# CT100-array.net
KiCad netlist of a schematic drawn in Altium Designer
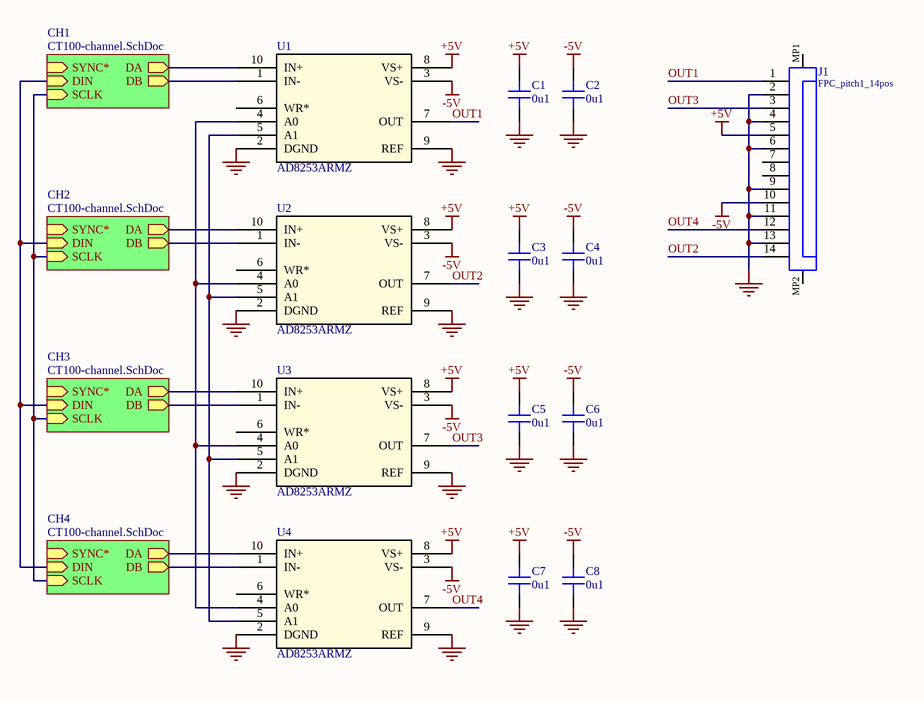
[diagram p0: CT100-array.SchDoc]

(export (version "E")
  (design (tool "Eeschema 10.0.6"))
  (components
    (comp (ref "C1")
      (value "0u1")
      (footprint "CAP_0402")
      (description "Capacitor SMD 0402")
      (fields (field (name "VOLTAGE") "50V"))
      (libsource (lib "symbols") (part "CAP_0402"))
    )
    (comp (ref "C2")
      (value "0u1")
      (footprint "CAP_0402")
      (description "Capacitor SMD 0402")
      (fields (field (name "VOLTAGE") "50V"))
      (libsource (lib "symbols") (part "CAP_0402"))
    )
    (comp (ref "C3")
      (value "0u1")
      (footprint "CAP_0402")
      (description "Capacitor SMD 0402")
      (fields (field (name "VOLTAGE") "50V"))
      (libsource (lib "symbols") (part "CAP_0402"))
    )
    (comp (ref "C4")
      (value "0u1")
      (footprint "CAP_0402")
      (description "Capacitor SMD 0402")
      (fields (field (name "VOLTAGE") "50V"))
      (libsource (lib "symbols") (part "CAP_0402"))
    )
    (comp (ref "C5")
      (value "0u1")
      (footprint "CAP_0402")
      (description "Capacitor SMD 0402")
      (fields (field (name "VOLTAGE") "50V"))
      (libsource (lib "symbols") (part "CAP_0402"))
    )
    (comp (ref "C6")
      (value "0u1")
      (footprint "CAP_0402")
      (description "Capacitor SMD 0402")
      (fields (field (name "VOLTAGE") "50V"))
      (libsource (lib "symbols") (part "CAP_0402"))
    )
    (comp (ref "C7")
      (value "0u1")
      (footprint "CAP_0402")
      (description "Capacitor SMD 0402")
      (fields (field (name "VOLTAGE") "50V"))
      (libsource (lib "symbols") (part "CAP_0402"))
    )
    (comp (ref "C8")
      (value "0u1")
      (footprint "CAP_0402")
      (description "Capacitor SMD 0402")
      (fields (field (name "VOLTAGE") "50V"))
      (libsource (lib "symbols") (part "CAP_0402"))
    )
    (comp (ref "J1")
      (value "FPC_pitch1_14pos")
      (footprint "FPC_pitch1_14pos")
      (description "14 Position 1 mm FFC & FPC Connectors")
      (libsource (lib "symbols") (part "FPC_pitch1_14pos"))
    )
    (comp (ref "U1")
      (value "AD8253ARMZ")
      (footprint "RM_10_ADI")
      (description "No Description Available")
      (fields (field (name "COPYRIGHT") "Copyright (C) 2023 Ultra Librarian. All rights reserved."))
      (libsource (lib "symbols") (part "AD8253ARMZ"))
    )
    (comp (ref "U2")
      (value "AD8253ARMZ")
      (footprint "RM_10_ADI")
      (description "No Description Available")
      (fields (field (name "COPYRIGHT") "Copyright (C) 2023 Ultra Librarian. All rights reserved."))
      (libsource (lib "symbols") (part "AD8253ARMZ"))
    )
    (comp (ref "U3")
      (value "AD8253ARMZ")
      (footprint "RM_10_ADI")
      (description "No Description Available")
      (fields (field (name "COPYRIGHT") "Copyright (C) 2023 Ultra Librarian. All rights reserved."))
      (libsource (lib "symbols") (part "AD8253ARMZ"))
    )
    (comp (ref "U4")
      (value "AD8253ARMZ")
      (footprint "RM_10_ADI")
      (description "No Description Available")
      (fields (field (name "COPYRIGHT") "Copyright (C) 2023 Ultra Librarian. All rights reserved."))
      (libsource (lib "symbols") (part "AD8253ARMZ"))
    )
  )
  (nets
    (net (code "1") (name "+5V") (class "Default")
      (node (ref "C1") (pin "1") (pinfunction "1_1") (pintype "passive"))
      (node (ref "C3") (pin "1") (pinfunction "1_1") (pintype "passive"))
      (node (ref "C5") (pin "1") (pinfunction "1_1") (pintype "passive"))
      (node (ref "C7") (pin "1") (pinfunction "1_1") (pintype "passive"))
      (node (ref "J1") (pin "5") (pinfunction "5_5") (pintype "passive"))
      (node (ref "U1") (pin "8") (pinfunction "VS+_8") (pintype "power_in"))
      (node (ref "U2") (pin "8") (pinfunction "VS+_8") (pintype "power_in"))
      (node (ref "U3") (pin "8") (pinfunction "VS+_8") (pintype "power_in"))
      (node (ref "U4") (pin "8") (pinfunction "VS+_8") (pintype "power_in"))
    )
    (net (code "2") (name "-5V") (class "Default")
      (node (ref "C2") (pin "1") (pinfunction "1_1") (pintype "passive"))
      (node (ref "C4") (pin "1") (pinfunction "1_1") (pintype "passive"))
      (node (ref "C6") (pin "1") (pinfunction "1_1") (pintype "passive"))
      (node (ref "C8") (pin "1") (pinfunction "1_1") (pintype "passive"))
      (node (ref "J1") (pin "10") (pinfunction "10_10") (pintype "passive"))
      (node (ref "U1") (pin "3") (pinfunction "VS-_3") (pintype "power_in"))
      (node (ref "U2") (pin "3") (pinfunction "VS-_3") (pintype "power_in"))
      (node (ref "U3") (pin "3") (pinfunction "VS-_3") (pintype "power_in"))
      (node (ref "U4") (pin "3") (pinfunction "VS-_3") (pintype "power_in"))
    )
    (net (code "3") (name "/DA") (class "Default")
      (node (ref "U1") (pin "10") (pinfunction "IN+_10") (pintype "passive"))
    )
    (net (code "4") (name "/DA_1") (class "Default")
      (node (ref "U4") (pin "10") (pinfunction "IN+_10") (pintype "passive"))
    )
    (net (code "5") (name "/DA_2") (class "Default")
      (node (ref "U3") (pin "10") (pinfunction "IN+_10") (pintype "passive"))
    )
    (net (code "6") (name "/DA_3") (class "Default")
      (node (ref "U2") (pin "10") (pinfunction "IN+_10") (pintype "passive"))
    )
    (net (code "7") (name "/DB") (class "Default")
      (node (ref "U1") (pin "1") (pinfunction "IN-_1") (pintype "passive"))
    )
    (net (code "8") (name "/DB_1") (class "Default")
      (node (ref "U4") (pin "1") (pinfunction "IN-_1") (pintype "passive"))
    )
    (net (code "9") (name "/DB_2") (class "Default")
      (node (ref "U3") (pin "1") (pinfunction "IN-_1") (pintype "passive"))
    )
    (net (code "10") (name "/DB_3") (class "Default")
      (node (ref "U2") (pin "1") (pinfunction "IN-_1") (pintype "passive"))
    )
    (net (code "12") (name "/OUT1") (class "Default")
      (node (ref "J1") (pin "1") (pinfunction "1_1") (pintype "passive"))
      (node (ref "U1") (pin "7") (pinfunction "OUT_7") (pintype "passive"))
    )
    (net (code "13") (name "/OUT2") (class "Default")
      (node (ref "J1") (pin "14") (pinfunction "14_14") (pintype "passive"))
      (node (ref "U2") (pin "7") (pinfunction "OUT_7") (pintype "passive"))
    )
    (net (code "14") (name "/OUT3") (class "Default")
      (node (ref "J1") (pin "3") (pinfunction "3_3") (pintype "passive"))
      (node (ref "U3") (pin "7") (pinfunction "OUT_7") (pintype "passive"))
    )
    (net (code "15") (name "/OUT4") (class "Default")
      (node (ref "J1") (pin "12") (pinfunction "12_12") (pintype "passive"))
      (node (ref "U4") (pin "7") (pinfunction "OUT_7") (pintype "passive"))
    )
    (net (code "21") (name "GND") (class "Default")
      (node (ref "C1") (pin "2") (pinfunction "2_2") (pintype "passive"))
      (node (ref "C2") (pin "2") (pinfunction "2_2") (pintype "passive"))
      (node (ref "C3") (pin "2") (pinfunction "2_2") (pintype "passive"))
      (node (ref "C4") (pin "2") (pinfunction "2_2") (pintype "passive"))
      (node (ref "C5") (pin "2") (pinfunction "2_2") (pintype "passive"))
      (node (ref "C6") (pin "2") (pinfunction "2_2") (pintype "passive"))
      (node (ref "C7") (pin "2") (pinfunction "2_2") (pintype "passive"))
      (node (ref "C8") (pin "2") (pinfunction "2_2") (pintype "passive"))
      (node (ref "J1") (pin "11") (pinfunction "11_11") (pintype "passive"))
      (node (ref "J1") (pin "13") (pinfunction "13_13") (pintype "passive"))
      (node (ref "J1") (pin "2") (pinfunction "2_2") (pintype "passive"))
      (node (ref "J1") (pin "4") (pinfunction "4_4") (pintype "passive"))
      (node (ref "J1") (pin "6") (pinfunction "6_6") (pintype "passive"))
      (node (ref "J1") (pin "9") (pinfunction "9_9") (pintype "passive"))
      (node (ref "U1") (pin "2") (pinfunction "DGND_2") (pintype "passive"))
      (node (ref "U1") (pin "9") (pinfunction "REF_9") (pintype "passive"))
      (node (ref "U2") (pin "2") (pinfunction "DGND_2") (pintype "passive"))
      (node (ref "U2") (pin "9") (pinfunction "REF_9") (pintype "passive"))
      (node (ref "U3") (pin "2") (pinfunction "DGND_2") (pintype "passive"))
      (node (ref "U3") (pin "9") (pinfunction "REF_9") (pintype "passive"))
      (node (ref "U4") (pin "2") (pinfunction "DGND_2") (pintype "passive"))
      (node (ref "U4") (pin "9") (pinfunction "REF_9") (pintype "passive"))
    )
    (net (code "22") (name "Net-(U1-A0)") (class "Default")
      (node (ref "U1") (pin "4") (pinfunction "A0_4") (pintype "passive"))
      (node (ref "U2") (pin "4") (pinfunction "A0_4") (pintype "passive"))
      (node (ref "U3") (pin "4") (pinfunction "A0_4") (pintype "passive"))
      (node (ref "U4") (pin "4") (pinfunction "A0_4") (pintype "passive"))
    )
    (net (code "23") (name "Net-(U1-A1)") (class "Default")
      (node (ref "U1") (pin "5") (pinfunction "A1_5") (pintype "passive"))
      (node (ref "U2") (pin "5") (pinfunction "A1_5") (pintype "passive"))
      (node (ref "U3") (pin "5") (pinfunction "A1_5") (pintype "passive"))
      (node (ref "U4") (pin "5") (pinfunction "A1_5") (pintype "passive"))
    )
    (net (code "24") (name "unconnected-(J1-Pad7)") (class "Default")
      (node (ref "J1") (pin "7") (pinfunction "7_7") (pintype "passive"))
    )
    (net (code "25") (name "unconnected-(J1-Pad8)") (class "Default")
      (node (ref "J1") (pin "8") (pinfunction "8_8") (pintype "passive"))
    )
    (net (code "26") (name "unconnected-(J1-PadMP1)") (class "Default")
      (node (ref "J1") (pin "MP1") (pinfunction "MP1_MP1") (pintype "passive"))
    )
    (net (code "27") (name "unconnected-(J1-PadMP2)") (class "Default")
      (node (ref "J1") (pin "MP2") (pinfunction "MP2_MP2") (pintype "passive"))
    )
    (net (code "28") (name "unconnected-(U1-WR*-Pad6)") (class "Default")
      (node (ref "U1") (pin "6") (pinfunction "WR*_6") (pintype "passive"))
    )
    (net (code "29") (name "unconnected-(U2-WR*-Pad6)") (class "Default")
      (node (ref "U2") (pin "6") (pinfunction "WR*_6") (pintype "passive"))
    )
    (net (code "30") (name "unconnected-(U3-WR*-Pad6)") (class "Default")
      (node (ref "U3") (pin "6") (pinfunction "WR*_6") (pintype "passive"))
    )
    (net (code "31") (name "unconnected-(U4-WR*-Pad6)") (class "Default")
      (node (ref "U4") (pin "6") (pinfunction "WR*_6") (pintype "passive"))
    )
  )
)
